# MDBU004A_DRV888x.net
KiCad netlist of a schematic drawn in Altium Designer
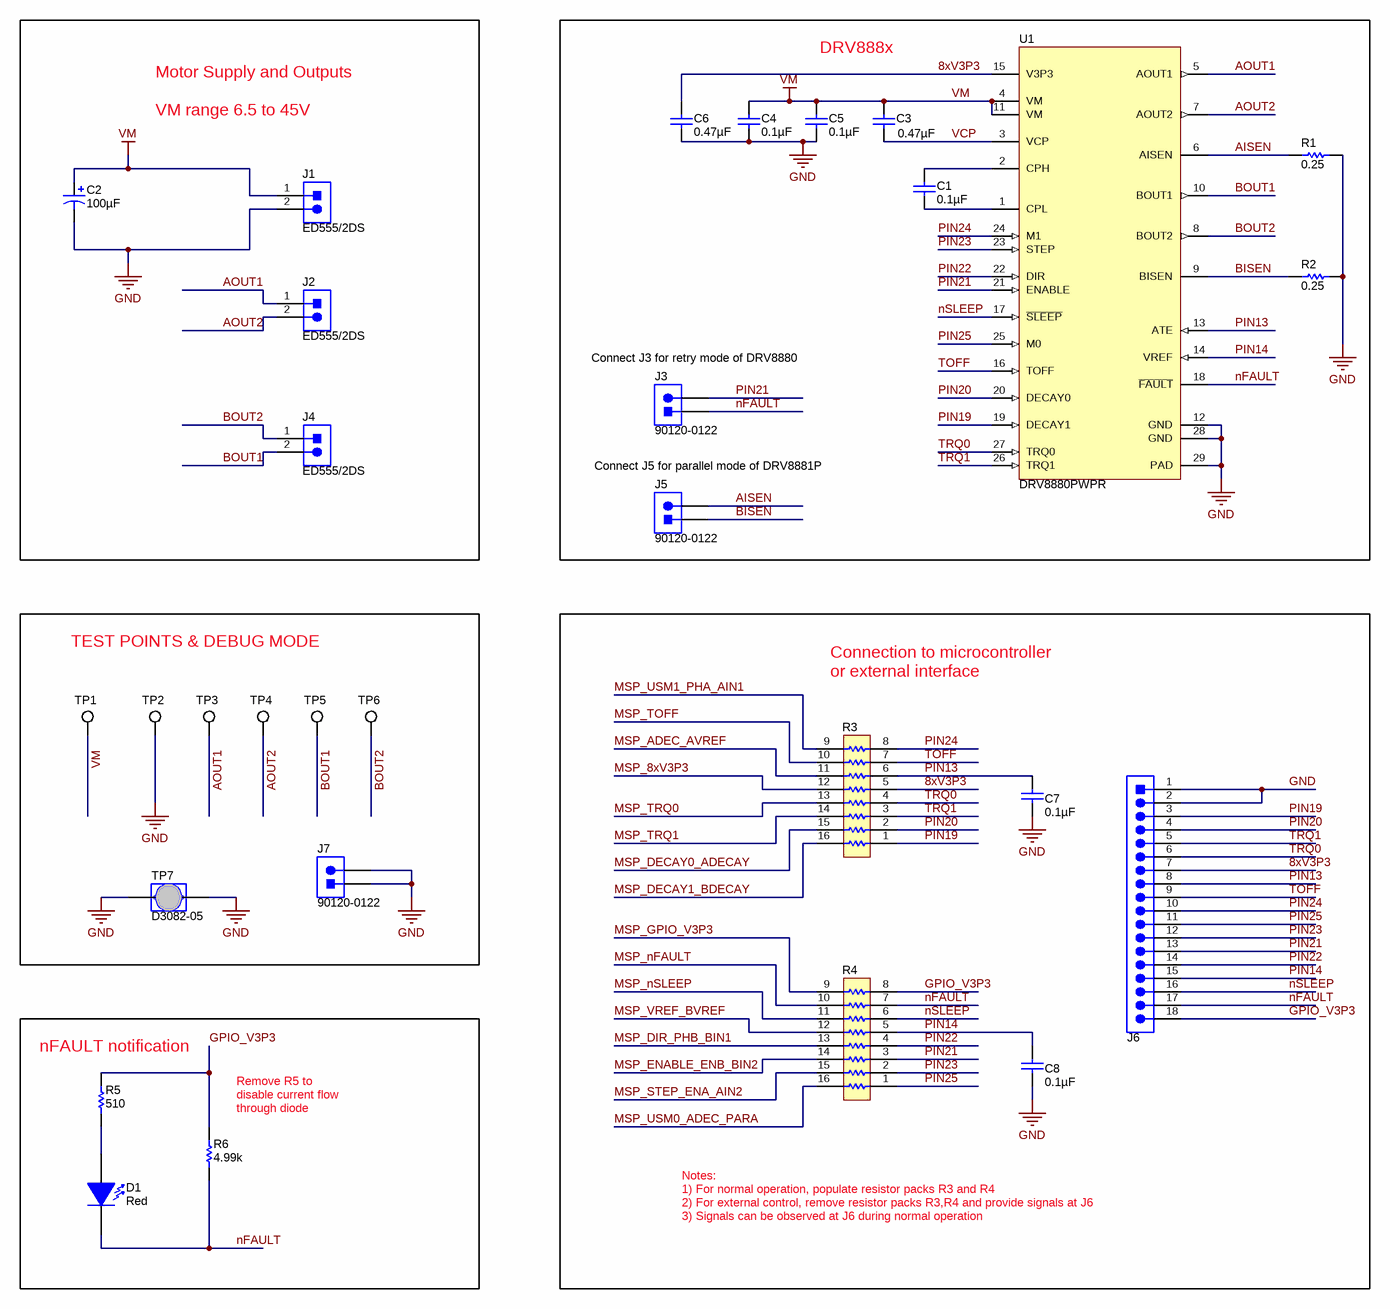
[diagram p0: MDBU004A_DRV888x.SchDoc]

(export (version "E")
  (design (tool "Eeschema 10.0.6"))
  (components
    (comp (ref "C1")
      (value "C0805C104K1RACTU")
      (footprint "0805L")
      (description "CAP, CERM, 0.1 µF, 100 V, +/- 10%, X7R, 0805")
      (fields
        (field (name "VALUEDISPLAYED") "0.1µF")
        (field (name "MANUFACTURER") "Kemet")
        (field (name "PUBLISHER") "Texas Instruments")
      )
      (libsource (lib "Capacitor_Ceramic") (part "C0805C104K1RACTU"))
    )
    (comp (ref "C2")
      (value "EEE-FK1J101P")
      (footprint "SM_RADIAL_G")
      (description "CAP, AL, 100 µF, 63 V, +/- 20%, 0.35 ohm, SMD")
      (fields
        (field (name "MANUFACTURER") "Panasonic")
        (field (name "VALUEDISPLAYED") "100µF")
        (field (name "PUBLISHER") "Texas Instruments")
      )
      (libsource (lib "Capacitor_Aluminum") (part "EEE-FK1J101P"))
    )
    (comp (ref "C3")
      (value "C2012X7R1E474K")
      (footprint "0805L")
      (description "CAP, CERM, 0.47 µF, 25 V, +/- 10%, X7R, 0805")
      (fields
        (field (name "VALUEDISPLAYED") "0.47µF")
        (field (name "MANUFACTURER") "TDK")
        (field (name "PUBLISHER") "Texas Instruments")
      )
      (libsource (lib "Capacitor_Ceramic") (part "C2012X7R1E474K"))
    )
    (comp (ref "C4")
      (value "C0805C104K1RACTU")
      (footprint "0805L")
      (description "CAP, CERM, 0.1 µF, 100 V, +/- 10%, X7R, 0805")
      (fields
        (field (name "VALUEDISPLAYED") "0.1µF")
        (field (name "MANUFACTURER") "Kemet")
        (field (name "PUBLISHER") "Texas Instruments")
      )
      (libsource (lib "Capacitor_Ceramic") (part "C0805C104K1RACTU"))
    )
    (comp (ref "C5")
      (value "C0805C104K1RACTU")
      (footprint "0805L")
      (description "CAP, CERM, 0.1 µF, 100 V, +/- 10%, X7R, 0805")
      (fields
        (field (name "VALUEDISPLAYED") "0.1µF")
        (field (name "MANUFACTURER") "Kemet")
        (field (name "PUBLISHER") "Texas Instruments")
      )
      (libsource (lib "Capacitor_Ceramic") (part "C0805C104K1RACTU"))
    )
    (comp (ref "C6")
      (value "C0603C474K9RACTU")
      (footprint "0603L")
      (description "CAP, CERM, 0.47 µF, 6.3 V, +/- 10%, X7R, 0603")
      (fields
        (field (name "VALUEDISPLAYED") "0.47µF")
        (field (name "MANUFACTURER") "Kemet")
        (field (name "PUBLISHER") "Texas Instruments")
      )
      (libsource (lib "Capacitor_Ceramic") (part "C0603C474K9RACTU"))
    )
    (comp (ref "C7")
      (value "GRM155R61A104KA01D")
      (footprint "0402L")
      (description "CAP, CERM, 0.1 µF, 10 V, +/- 10%, X5R, 0402")
      (fields
        (field (name "MANUFACTURER") "MuRata")
        (field (name "VALUEDISPLAYED") "0.1µF")
        (field (name "PUBLISHER") "Texas Instruments")
      )
      (libsource (lib "Capacitor_Ceramic") (part "GRM155R61A104KA01D"))
    )
    (comp (ref "C8")
      (value "GRM155R61A104KA01D")
      (footprint "0402L")
      (description "CAP, CERM, 0.1 µF, 10 V, +/- 10%, X5R, 0402")
      (fields
        (field (name "MANUFACTURER") "MuRata")
        (field (name "VALUEDISPLAYED") "0.1µF")
        (field (name "PUBLISHER") "Texas Instruments")
      )
      (libsource (lib "Capacitor_Ceramic") (part "GRM155R61A104KA01D"))
    )
    (comp (ref "D1")
      (value "Red")
      (footprint "LED_LTST-C190_Red")
      (description "LED, Red, SMD")
      (fields
        (field (name "PARTNUMBER") "LTST-C190CKT")
        (field (name "MANUFACTURER") "Lite-On")
        (field (name "PUBLISHER") "Texas Instruments")
      )
      (libsource (lib "LED") (part "LTST-C190CKT"))
    )
    (comp (ref "J1")
      (value "ED555/2DS")
      (footprint "TERM_BLK_ED555-2DS")
      (description "Terminal Block, 6A, 3.5mm Pitch, 2-Pos, TH")
      (fields
        (field (name "MANUFACTURER") "On-Shore Technology")
        (field (name "SYMBOLCREATOR") "a0412235")
        (field (name "PUBLISHER") "Texas Instruments")
      )
      (libsource (lib "Connectors_Other") (part "ED555/2DS"))
    )
    (comp (ref "J2")
      (value "ED555/2DS")
      (footprint "TERM_BLK_ED555-2DS")
      (description "Terminal Block, 6A, 3.5mm Pitch, 2-Pos, TH")
      (fields
        (field (name "MANUFACTURER") "On-Shore Technology")
        (field (name "SYMBOLCREATOR") "a0412235")
        (field (name "PUBLISHER") "Texas Instruments")
      )
      (libsource (lib "Connectors_Other") (part "ED555/2DS"))
    )
    (comp (ref "J3")
      (value "90120-0122")
      (footprint "CONN_90120-0122")
      (description "Header, 100mil, 2x1, Tin, TH")
      (fields
        (field (name "MANUFACTURER") "Molex")
        (field (name "SYMBOLCREATOR") "a0412235")
        (field (name "PUBLISHER") "Texas Instruments")
      )
      (libsource (lib "Connectors_Molex") (part "90120-0122"))
    )
    (comp (ref "J4")
      (value "ED555/2DS")
      (footprint "TERM_BLK_ED555-2DS")
      (description "Terminal Block, 6A, 3.5mm Pitch, 2-Pos, TH")
      (fields
        (field (name "MANUFACTURER") "On-Shore Technology")
        (field (name "SYMBOLCREATOR") "a0412235")
        (field (name "PUBLISHER") "Texas Instruments")
      )
      (libsource (lib "Connectors_Other") (part "ED555/2DS"))
    )
    (comp (ref "J5")
      (value "90120-0122")
      (footprint "CONN_90120-0122")
      (description "Header, 100mil, 2x1, Tin, TH")
      (fields
        (field (name "MANUFACTURER") "Molex")
        (field (name "SYMBOLCREATOR") "a0412235")
        (field (name "PUBLISHER") "Texas Instruments")
      )
      (libsource (lib "Connectors_Molex") (part "90120-0122"))
    )
    (comp (ref "J6")
      (value "TSW-118-07-G-S")
      (footprint "TSW-118-07-G-S")
      (description "Header, 100mil, 18x1, Gold, TH")
      (fields
        (field (name "MANUFACTURER") "Samtec")
        (field (name "SYMBOLCREATOR") "a0411947")
        (field (name "PUBLISHER") "Texas Instruments")
      )
      (libsource (lib "Connectors_Samtec") (part "TSW-118-07-G-S"))
    )
    (comp (ref "J7")
      (value "90120-0122")
      (footprint "CONN_90120-0122")
      (description "Header, 100mil, 2x1, Tin, TH")
      (fields
        (field (name "MANUFACTURER") "Molex")
        (field (name "SYMBOLCREATOR") "a0412235")
        (field (name "PUBLISHER") "Texas Instruments")
      )
      (libsource (lib "Connectors_Molex") (part "90120-0122"))
    )
    (comp (ref "R1")
      (value "0.25")
      (footprint "2010L")
      (description "RES, 0.25, 1%, 1 W, 2010")
      (fields
        (field (name "PARTNUMBER") "CSRN2010FKR250")
        (field (name "MANUFACTURER") "Stackpole Electronics Inc")
        (field (name "PUBLISHER") "Texas Instruments")
      )
      (libsource (lib "Resistor_2010") (part "CSRN2010FKR250"))
    )
    (comp (ref "R2")
      (value "0.25")
      (footprint "2010L")
      (description "RES, 0.25, 1%, 1 W, 2010")
      (fields
        (field (name "PARTNUMBER") "CSRN2010FKR250")
        (field (name "MANUFACTURER") "Stackpole Electronics Inc")
        (field (name "PUBLISHER") "Texas Instruments")
      )
      (libsource (lib "Resistor_2010") (part "CSRN2010FKR250"))
    )
    (comp (ref "R3")
      (value "EXB-2HV330JV")
      (footprint "RESCAXS_EXB-2HV")
      (description "RES, 33, 5%, 0.0625 W, Resistor Array - 8x1")
      (fields
        (field (name "MANUFACTURER") "Panasonic")
        (field (name "SYMBOLCREATOR") "a0411947")
        (field (name "PUBLISHER") "Texas Instruments")
      )
      (libsource (lib "Resistor_OtherSMT") (part "EXB-2HV330JV"))
    )
    (comp (ref "R4")
      (value "EXB-2HV330JV")
      (footprint "RESCAXS_EXB-2HV")
      (description "RES, 33, 5%, 0.0625 W, Resistor Array - 8x1")
      (fields
        (field (name "MANUFACTURER") "Panasonic")
        (field (name "SYMBOLCREATOR") "a0411947")
        (field (name "PUBLISHER") "Texas Instruments")
      )
      (libsource (lib "Resistor_OtherSMT") (part "EXB-2HV330JV"))
    )
    (comp (ref "R5")
      (value "510")
      (footprint "0402L")
      (description "RES, 510, 5%, 0.063 W, 0402")
      (fields
        (field (name "PARTNUMBER") "CRCW0402510RJNED")
        (field (name "MANUFACTURER") "Vishay-Dale")
        (field (name "PUBLISHER") "Texas Instruments")
      )
      (libsource (lib "Resistor_0402") (part "CRCW0402510RJNED"))
    )
    (comp (ref "R6")
      (value "4.99k")
      (footprint "0402L")
      (description "RES, 4.99 k, 1%, 0.063 W, 0402")
      (fields
        (field (name "PARTNUMBER") "CRCW04024K99FKED")
        (field (name "MANUFACTURER") "Vishay-Dale")
        (field (name "PUBLISHER") "Texas Instruments")
      )
      (libsource (lib "Resistor_0402") (part "CRCW04024K99FKED"))
    )
    (comp (ref "TP1")
      (value "5016")
      (footprint "Testpoint_Keystone_Compact")
      (description "Test Point, Compact, SMT")
      (fields (field (name "MANUFACTURER") "Keystone") (field (name "PUBLISHER") "Texas Instruments"))
      (libsource (lib "Connectors_Keystone") (part "5016"))
    )
    (comp (ref "TP2")
      (value "5016")
      (footprint "Testpoint_Keystone_Compact")
      (description "Test Point, Compact, SMT")
      (fields (field (name "MANUFACTURER") "Keystone") (field (name "PUBLISHER") "Texas Instruments"))
      (libsource (lib "Connectors_Keystone") (part "5016"))
    )
    (comp (ref "TP3")
      (value "5016")
      (footprint "Testpoint_Keystone_Compact")
      (description "Test Point, Compact, SMT")
      (fields (field (name "MANUFACTURER") "Keystone") (field (name "PUBLISHER") "Texas Instruments"))
      (libsource (lib "Connectors_Keystone") (part "5016"))
    )
    (comp (ref "TP4")
      (value "5016")
      (footprint "Testpoint_Keystone_Compact")
      (description "Test Point, Compact, SMT")
      (fields (field (name "MANUFACTURER") "Keystone") (field (name "PUBLISHER") "Texas Instruments"))
      (libsource (lib "Connectors_Keystone") (part "5016"))
    )
    (comp (ref "TP5")
      (value "5016")
      (footprint "Testpoint_Keystone_Compact")
      (description "Test Point, Compact, SMT")
      (fields (field (name "MANUFACTURER") "Keystone") (field (name "PUBLISHER") "Texas Instruments"))
      (libsource (lib "Connectors_Keystone") (part "5016"))
    )
    (comp (ref "TP6")
      (value "5016")
      (footprint "Testpoint_Keystone_Compact")
      (description "Test Point, Compact, SMT")
      (fields (field (name "MANUFACTURER") "Keystone") (field (name "PUBLISHER") "Texas Instruments"))
      (libsource (lib "Connectors_Keystone") (part "5016"))
    )
    (comp (ref "TP7")
      (value "D3082-05")
      (footprint "Harwin_D3082-05")
      (description "1mm Uninsulated Shorting Plug, 10.16mm spacing, TH")
      (fields
        (field (name "MANUFACTURER") "Harwin")
        (field (name "SYMBOLCREATOR") "a0799628")
        (field (name "PUBLISHER") "Texas Instruments")
      )
      (libsource (lib "Connectors_Other") (part "D3082-05"))
    )
    (comp (ref "U1")
      (value "DRV8880PWPR")
      (footprint "PWP0028C_N")
      (description "2-A 45-V 1/16-μstep Stepper Motor Driver With AutoTune, PWP0028C")
      (fields
        (field (name "ALTERNATE PARTNUMBER") "DRV8880PWP")
        (field (name "MANUFACTURER") "Texas Instruments")
        (field (name "SYMBOLCREATOR") "Altium")
        (field (name "PUBLISHER") "Texas Instruments")
      )
      (libsource (lib "TI_Pre_RTM") (part "DRV8880PWPR"))
    )
  )
  (nets
    (net (code "1") (name "/8xV3P3") (class "Default")
      (node (ref "C6") (pin "1") (pinfunction "1_1") (pintype "passive"))
      (node (ref "J6") (pin "7") (pinfunction "7_7") (pintype "passive"))
      (node (ref "R3") (pin "5") (pinfunction "5_5") (pintype "passive"))
      (node (ref "U1") (pin "15") (pinfunction "V3P3_15") (pintype "power_in"))
    )
    (net (code "2") (name "/AISEN") (class "Default")
      (node (ref "J5") (pin "2") (pinfunction "2_2") (pintype "passive"))
      (node (ref "R1") (pin "2") (pinfunction "2_2") (pintype "passive"))
      (node (ref "U1") (pin "6") (pinfunction "AISEN_6") (pintype "passive"))
    )
    (net (code "3") (name "/AOUT1") (class "Default")
      (node (ref "J2") (pin "1") (pinfunction "1_1") (pintype "passive"))
      (node (ref "TP3") (pin "1") (pintype "passive"))
      (node (ref "U1") (pin "5") (pinfunction "AOUT1_5") (pintype "output"))
    )
    (net (code "4") (name "/AOUT2") (class "Default")
      (node (ref "J2") (pin "2") (pinfunction "2_2") (pintype "passive"))
      (node (ref "TP4") (pin "1") (pintype "passive"))
      (node (ref "U1") (pin "7") (pinfunction "AOUT2_7") (pintype "output"))
    )
    (net (code "5") (name "/BISEN") (class "Default")
      (node (ref "J5") (pin "1") (pinfunction "1_1") (pintype "passive"))
      (node (ref "R2") (pin "2") (pinfunction "2_2") (pintype "passive"))
      (node (ref "U1") (pin "9") (pinfunction "BISEN_9") (pintype "passive"))
    )
    (net (code "6") (name "/BOUT1") (class "Default")
      (node (ref "J4") (pin "2") (pinfunction "2_2") (pintype "passive"))
      (node (ref "TP5") (pin "1") (pintype "passive"))
      (node (ref "U1") (pin "10") (pinfunction "BOUT1_10") (pintype "output"))
    )
    (net (code "7") (name "/BOUT2") (class "Default")
      (node (ref "J4") (pin "1") (pinfunction "1_1") (pintype "passive"))
      (node (ref "TP6") (pin "1") (pintype "passive"))
      (node (ref "U1") (pin "8") (pinfunction "BOUT2_8") (pintype "output"))
    )
    (net (code "8") (name "/GPIO_V3P3") (class "Default")
      (node (ref "J6") (pin "18") (pinfunction "18_18") (pintype "passive"))
      (node (ref "R4") (pin "8") (pinfunction "8_8") (pintype "passive"))
      (node (ref "R5") (pin "2") (pinfunction "2_2") (pintype "passive"))
      (node (ref "R6") (pin "2") (pinfunction "2_2") (pintype "passive"))
    )
    (net (code "9") (name "/MSP_8xV3P3") (class "Default")
      (node (ref "R3") (pin "12") (pinfunction "12_12") (pintype "passive"))
    )
    (net (code "10") (name "/MSP_ADEC_AVREF") (class "Default")
      (node (ref "R3") (pin "11") (pinfunction "11_11") (pintype "passive"))
    )
    (net (code "11") (name "/MSP_DECAY0_ADECAY") (class "Default")
      (node (ref "R3") (pin "15") (pinfunction "15_15") (pintype "passive"))
    )
    (net (code "12") (name "/MSP_DECAY1_BDECAY") (class "Default")
      (node (ref "R3") (pin "16") (pinfunction "16_16") (pintype "passive"))
    )
    (net (code "13") (name "/MSP_DIR_PHB_BIN1") (class "Default")
      (node (ref "R4") (pin "13") (pinfunction "13_13") (pintype "passive"))
    )
    (net (code "14") (name "/MSP_ENABLE_ENB_BIN2") (class "Default")
      (node (ref "R4") (pin "14") (pinfunction "14_14") (pintype "passive"))
    )
    (net (code "15") (name "/MSP_GPIO_V3P3") (class "Default")
      (node (ref "R4") (pin "9") (pinfunction "9_9") (pintype "passive"))
    )
    (net (code "16") (name "/MSP_STEP_ENA_AIN2") (class "Default")
      (node (ref "R4") (pin "15") (pinfunction "15_15") (pintype "passive"))
    )
    (net (code "17") (name "/MSP_TOFF") (class "Default")
      (node (ref "R3") (pin "10") (pinfunction "10_10") (pintype "passive"))
    )
    (net (code "18") (name "/MSP_TRQ0") (class "Default")
      (node (ref "R3") (pin "13") (pinfunction "13_13") (pintype "passive"))
    )
    (net (code "19") (name "/MSP_TRQ1") (class "Default")
      (node (ref "R3") (pin "14") (pinfunction "14_14") (pintype "passive"))
    )
    (net (code "20") (name "/MSP_USM0_ADEC_PARA") (class "Default")
      (node (ref "R4") (pin "16") (pinfunction "16_16") (pintype "passive"))
    )
    (net (code "21") (name "/MSP_USM1_PHA_AIN1") (class "Default")
      (node (ref "R3") (pin "9") (pinfunction "9_9") (pintype "passive"))
    )
    (net (code "22") (name "/MSP_VREF_BVREF") (class "Default")
      (node (ref "R4") (pin "12") (pinfunction "12_12") (pintype "passive"))
    )
    (net (code "23") (name "/MSP_nFAULT") (class "Default")
      (node (ref "R4") (pin "10") (pinfunction "10_10") (pintype "passive"))
    )
    (net (code "24") (name "/MSP_nSLEEP") (class "Default")
      (node (ref "R4") (pin "11") (pinfunction "11_11") (pintype "passive"))
    )
    (net (code "25") (name "/PIN13") (class "Default")
      (node (ref "C7") (pin "1") (pinfunction "1_1") (pintype "passive"))
      (node (ref "J6") (pin "8") (pinfunction "8_8") (pintype "passive"))
      (node (ref "R3") (pin "6") (pinfunction "6_6") (pintype "passive"))
      (node (ref "U1") (pin "13") (pinfunction "ATE_13") (pintype "input"))
    )
    (net (code "26") (name "/PIN14") (class "Default")
      (node (ref "C8") (pin "1") (pinfunction "1_1") (pintype "passive"))
      (node (ref "J6") (pin "15") (pinfunction "15_15") (pintype "passive"))
      (node (ref "R4") (pin "5") (pinfunction "5_5") (pintype "passive"))
      (node (ref "U1") (pin "14") (pinfunction "VREF_14") (pintype "input"))
    )
    (net (code "27") (name "/PIN19") (class "Default")
      (node (ref "J6") (pin "3") (pinfunction "3_3") (pintype "passive"))
      (node (ref "R3") (pin "1") (pinfunction "1_1") (pintype "passive"))
      (node (ref "U1") (pin "19") (pinfunction "DECAY1_19") (pintype "input"))
    )
    (net (code "28") (name "/PIN20") (class "Default")
      (node (ref "J6") (pin "4") (pinfunction "4_4") (pintype "passive"))
      (node (ref "R3") (pin "2") (pinfunction "2_2") (pintype "passive"))
      (node (ref "U1") (pin "20") (pinfunction "DECAY0_20") (pintype "input"))
    )
    (net (code "29") (name "/PIN21") (class "Default")
      (node (ref "J3") (pin "2") (pinfunction "2_2") (pintype "passive"))
      (node (ref "J6") (pin "13") (pinfunction "13_13") (pintype "passive"))
      (node (ref "R4") (pin "3") (pinfunction "3_3") (pintype "passive"))
      (node (ref "U1") (pin "21") (pinfunction "ENABLE_21") (pintype "input"))
    )
    (net (code "30") (name "/PIN22") (class "Default")
      (node (ref "J6") (pin "14") (pinfunction "14_14") (pintype "passive"))
      (node (ref "R4") (pin "4") (pinfunction "4_4") (pintype "passive"))
      (node (ref "U1") (pin "22") (pinfunction "DIR_22") (pintype "input"))
    )
    (net (code "31") (name "/PIN23") (class "Default")
      (node (ref "J6") (pin "12") (pinfunction "12_12") (pintype "passive"))
      (node (ref "R4") (pin "2") (pinfunction "2_2") (pintype "passive"))
      (node (ref "U1") (pin "23") (pinfunction "STEP_23") (pintype "input"))
    )
    (net (code "32") (name "/PIN24") (class "Default")
      (node (ref "J6") (pin "10") (pinfunction "10_10") (pintype "passive"))
      (node (ref "R3") (pin "8") (pinfunction "8_8") (pintype "passive"))
      (node (ref "U1") (pin "24") (pinfunction "M1_24") (pintype "input"))
    )
    (net (code "33") (name "/PIN25") (class "Default")
      (node (ref "J6") (pin "11") (pinfunction "11_11") (pintype "passive"))
      (node (ref "R4") (pin "1") (pinfunction "1_1") (pintype "passive"))
      (node (ref "U1") (pin "25") (pinfunction "M0_25") (pintype "input"))
    )
    (net (code "34") (name "/TOFF") (class "Default")
      (node (ref "J6") (pin "9") (pinfunction "9_9") (pintype "passive"))
      (node (ref "R3") (pin "7") (pinfunction "7_7") (pintype "passive"))
      (node (ref "U1") (pin "16") (pinfunction "TOFF_16") (pintype "input"))
    )
    (net (code "35") (name "/TRQ0") (class "Default")
      (node (ref "J6") (pin "6") (pinfunction "6_6") (pintype "passive"))
      (node (ref "R3") (pin "4") (pinfunction "4_4") (pintype "passive"))
      (node (ref "U1") (pin "27") (pinfunction "TRQ0_27") (pintype "input"))
    )
    (net (code "36") (name "/TRQ1") (class "Default")
      (node (ref "J6") (pin "5") (pinfunction "5_5") (pintype "passive"))
      (node (ref "R3") (pin "3") (pinfunction "3_3") (pintype "passive"))
      (node (ref "U1") (pin "26") (pinfunction "TRQ1_26") (pintype "input"))
    )
    (net (code "37") (name "/VCP") (class "Default")
      (node (ref "C3") (pin "1") (pinfunction "1_1") (pintype "passive"))
      (node (ref "U1") (pin "3") (pinfunction "VCP_3") (pintype "passive"))
    )
    (net (code "38") (name "/nFAULT") (class "Default")
      (node (ref "D1") (pin "2") (pinfunction "K_2") (pintype "passive"))
      (node (ref "J3") (pin "1") (pinfunction "1_1") (pintype "passive"))
      (node (ref "J6") (pin "17") (pinfunction "17_17") (pintype "passive"))
      (node (ref "R4") (pin "7") (pinfunction "7_7") (pintype "passive"))
      (node (ref "R6") (pin "1") (pinfunction "1_1") (pintype "passive"))
      (node (ref "U1") (pin "18") (pinfunction "FAULT_18") (pintype "open_collector"))
    )
    (net (code "39") (name "/nSLEEP") (class "Default")
      (node (ref "J6") (pin "16") (pinfunction "16_16") (pintype "passive"))
      (node (ref "R4") (pin "6") (pinfunction "6_6") (pintype "passive"))
      (node (ref "U1") (pin "17") (pinfunction "SLEEP_17") (pintype "input"))
    )
    (net (code "40") (name "GND") (class "Default")
      (node (ref "C2") (pin "2") (pinfunction "-_2") (pintype "passive"))
      (node (ref "C4") (pin "1") (pinfunction "1_1") (pintype "passive"))
      (node (ref "C5") (pin "1") (pinfunction "1_1") (pintype "passive"))
      (node (ref "C6") (pin "2") (pinfunction "2_2") (pintype "passive"))
      (node (ref "C7") (pin "2") (pinfunction "2_2") (pintype "passive"))
      (node (ref "C8") (pin "2") (pinfunction "2_2") (pintype "passive"))
      (node (ref "J1") (pin "2") (pinfunction "2_2") (pintype "passive"))
      (node (ref "J6") (pin "1") (pinfunction "1_1") (pintype "passive"))
      (node (ref "J6") (pin "2") (pinfunction "2_2") (pintype "passive"))
      (node (ref "J7") (pin "1") (pinfunction "1_1") (pintype "passive"))
      (node (ref "J7") (pin "2") (pinfunction "2_2") (pintype "passive"))
      (node (ref "R1") (pin "1") (pinfunction "1_1") (pintype "passive"))
      (node (ref "R2") (pin "1") (pinfunction "1_1") (pintype "passive"))
      (node (ref "TP2") (pin "1") (pintype "passive"))
      (node (ref "TP7") (pin "1") (pinfunction "1_1") (pintype "passive"))
      (node (ref "TP7") (pin "2") (pinfunction "2_2") (pintype "passive"))
      (node (ref "U1") (pin "12") (pinfunction "GND_12") (pintype "power_in"))
      (node (ref "U1") (pin "28") (pinfunction "GND_28") (pintype "power_in"))
      (node (ref "U1") (pin "29") (pinfunction "PAD_29") (pintype "power_in"))
    )
    (net (code "41") (name "Net-(D1-A)") (class "Default")
      (node (ref "D1") (pin "1") (pinfunction "A_1") (pintype "passive"))
      (node (ref "R5") (pin "1") (pinfunction "1_1") (pintype "passive"))
    )
    (net (code "42") (name "Net-(U1-CPH)") (class "Default")
      (node (ref "C1") (pin "2") (pinfunction "2_2") (pintype "passive"))
      (node (ref "U1") (pin "2") (pinfunction "CPH_2") (pintype "passive"))
    )
    (net (code "43") (name "Net-(U1-CPL)") (class "Default")
      (node (ref "C1") (pin "1") (pinfunction "1_1") (pintype "passive"))
      (node (ref "U1") (pin "1") (pinfunction "CPL_1") (pintype "passive"))
    )
    (net (code "44") (name "VM") (class "Default")
      (node (ref "C2") (pin "1") (pinfunction "+_1") (pintype "passive"))
      (node (ref "C3") (pin "2") (pinfunction "2_2") (pintype "passive"))
      (node (ref "C4") (pin "2") (pinfunction "2_2") (pintype "passive"))
      (node (ref "C5") (pin "2") (pinfunction "2_2") (pintype "passive"))
      (node (ref "J1") (pin "1") (pinfunction "1_1") (pintype "passive"))
      (node (ref "TP1") (pin "1") (pintype "passive"))
      (node (ref "U1") (pin "11") (pinfunction "VM_11") (pintype "power_in"))
      (node (ref "U1") (pin "4") (pinfunction "VM_4") (pintype "power_in"))
    )
  )
)
